# Main.net
KiCad netlist of a schematic drawn in Altium Designer
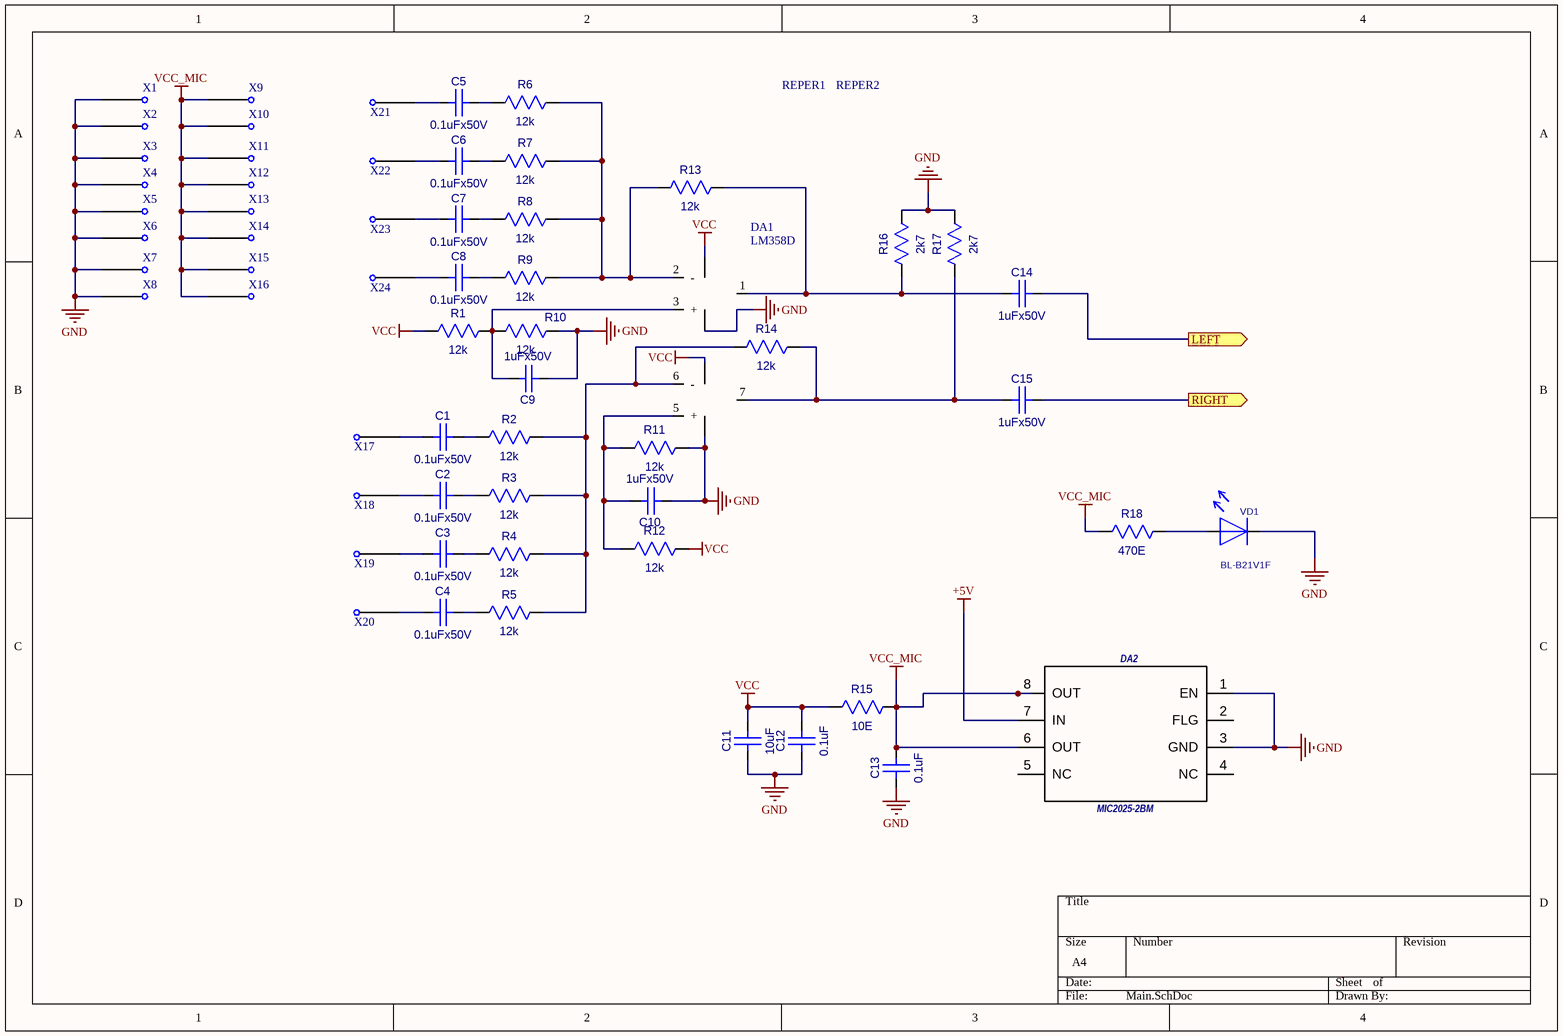
[diagram p0: Main.SchDoc]

(export (version "E")
  (design (tool "Eeschema 10.0.6"))
  (components
    (comp (ref "C1")
      (value "0.1uFx50V")
      (footprint "CC0603-3M")
      (description "CC0603 X7R")
      (libsource (lib "gprs_modem") (part "CC0603"))
    )
    (comp (ref "C2")
      (value "0.1uFx50V")
      (footprint "CC0603-3M")
      (description "CC0603 X7R")
      (libsource (lib "gprs_modem") (part "CC0603"))
    )
    (comp (ref "C3")
      (value "0.1uFx50V")
      (footprint "CC0603-3M")
      (description "CC0603 X7R")
      (libsource (lib "gprs_modem") (part "CC0603"))
    )
    (comp (ref "C4")
      (value "0.1uFx50V")
      (footprint "CC0603-3M")
      (description "CC0603 X7R")
      (libsource (lib "gprs_modem") (part "CC0603"))
    )
    (comp (ref "C5")
      (value "0.1uFx50V")
      (footprint "CC0603-3M")
      (description "CC0603 X7R")
      (libsource (lib "gprs_modem") (part "CC0603"))
    )
    (comp (ref "C6")
      (value "0.1uFx50V")
      (footprint "CC0603-3M")
      (description "CC0603 X7R")
      (libsource (lib "gprs_modem") (part "CC0603"))
    )
    (comp (ref "C7")
      (value "0.1uFx50V")
      (footprint "CC0603-3M")
      (description "CC0603 X7R")
      (libsource (lib "gprs_modem") (part "CC0603"))
    )
    (comp (ref "C8")
      (value "0.1uFx50V")
      (footprint "CC0603-3M")
      (description "CC0603 X7R")
      (libsource (lib "gprs_modem") (part "CC0603"))
    )
    (comp (ref "C9")
      (value "1uFx50V")
      (footprint "CC0603-3M")
      (description "CC0603 X7R")
      (libsource (lib "gprs_modem") (part "CC0603"))
    )
    (comp (ref "C10")
      (value "1uFx50V")
      (footprint "CC0603-3M")
      (description "CC0603 X7R")
      (libsource (lib "gprs_modem") (part "CC0603"))
    )
    (comp (ref "C11")
      (value "10uF")
      (footprint "CC0805-MIDI-2M1")
      (description "CC0805")
      (libsource (lib "gprs_modem") (part "CC0805"))
    )
    (comp (ref "C12")
      (value "0.1uF")
      (footprint "CC0603-3M")
      (description "CC0603")
      (libsource (lib "gprs_modem") (part "CC0603"))
    )
    (comp (ref "C13")
      (value "0.1uF")
      (footprint "CC0603-3M")
      (description "CC0603")
      (libsource (lib "gprs_modem") (part "CC0603"))
    )
    (comp (ref "C14")
      (value "1uFx50V")
      (footprint "CC0603-3M")
      (description "CC0603 X7R")
      (libsource (lib "gprs_modem") (part "CC0603"))
    )
    (comp (ref "C15")
      (value "1uFx50V")
      (footprint "CC0603-3M")
      (description "CC0603 X7R")
      (libsource (lib "gprs_modem") (part "CC0603"))
    )
    (comp (ref "DA1") (value "LM358D") (footprint "SO-8") (libsource (lib "VHF") (part "LM358D")))
    (comp (ref "DA2") (value "MIC2025-2BM") (footprint "SO-8") (libsource (lib "*") (part "MIC2025-2BM")))
    (comp (ref "R1")
      (value "12k")
      (footprint "RC0603-3M")
      (description "RC0603")
      (libsource (lib "gprs_modem") (part "RC0603"))
    )
    (comp (ref "R2")
      (value "12k")
      (footprint "RC0603-3M")
      (description "RC0603")
      (libsource (lib "gprs_modem") (part "RC0603"))
    )
    (comp (ref "R3")
      (value "12k")
      (footprint "RC0603-3M")
      (description "RC0603")
      (libsource (lib "gprs_modem") (part "RC0603"))
    )
    (comp (ref "R4")
      (value "12k")
      (footprint "RC0603-3M")
      (description "RC0603")
      (libsource (lib "gprs_modem") (part "RC0603"))
    )
    (comp (ref "R5")
      (value "12k")
      (footprint "RC0603-3M")
      (description "RC0603")
      (libsource (lib "gprs_modem") (part "RC0603"))
    )
    (comp (ref "R6")
      (value "12k")
      (footprint "RC0603-3M")
      (description "RC0603")
      (libsource (lib "gprs_modem") (part "RC0603"))
    )
    (comp (ref "R7")
      (value "12k")
      (footprint "RC0603-3M")
      (description "RC0603")
      (libsource (lib "gprs_modem") (part "RC0603"))
    )
    (comp (ref "R8")
      (value "12k")
      (footprint "RC0603-3M")
      (description "RC0603")
      (libsource (lib "gprs_modem") (part "RC0603"))
    )
    (comp (ref "R9")
      (value "12k")
      (footprint "RC0603-3M")
      (description "RC0603")
      (libsource (lib "gprs_modem") (part "RC0603"))
    )
    (comp (ref "R10")
      (value "12k")
      (footprint "RC0603-3M")
      (description "RC0603")
      (libsource (lib "gprs_modem") (part "RC0603"))
    )
    (comp (ref "R11")
      (value "12k")
      (footprint "RC0603-3M")
      (description "RC0603")
      (libsource (lib "gprs_modem") (part "RC0603"))
    )
    (comp (ref "R12")
      (value "12k")
      (footprint "RC0603-3M")
      (description "RC0603")
      (libsource (lib "gprs_modem") (part "RC0603"))
    )
    (comp (ref "R13")
      (value "12k")
      (footprint "RC0603-3M")
      (description "RC0603")
      (libsource (lib "gprs_modem") (part "RC0603"))
    )
    (comp (ref "R14")
      (value "12k")
      (footprint "RC0603-3M")
      (description "RC0603")
      (libsource (lib "gprs_modem") (part "RC0603"))
    )
    (comp (ref "R15")
      (value "10E")
      (footprint "RC0805_IPC_NOM")
      (description "RC0805")
      (libsource (lib "gprs_modem") (part "RC0805"))
    )
    (comp (ref "R16")
      (value "2k7")
      (footprint "RC0603-3M")
      (description "RC0603")
      (libsource (lib "gprs_modem") (part "RC0603"))
    )
    (comp (ref "R17")
      (value "2k7")
      (footprint "RC0603-3M")
      (description "RC0603")
      (libsource (lib "gprs_modem") (part "RC0603"))
    )
    (comp (ref "R18")
      (value "470E")
      (footprint "RC0603-3M")
      (description "RC0603")
      (libsource (lib "gprs_modem") (part "RC0603"))
    )
    (comp (ref "REPER1")
      (value "REPER1.2")
      (footprint "REPER1.2")
      (libsource (lib "gprs_modem") (part "REPER1.2"))
    )
    (comp (ref "REPER2")
      (value "REPER1.2")
      (footprint "REPER1.2")
      (libsource (lib "gprs_modem") (part "REPER1.2"))
    )
    (comp (ref "VD1")
      (value "BL-B21V1F")
      (footprint "LED3")
      (description "LED_3")
      (libsource (lib "gprs_modem") (part "LED_3"))
    )
    (comp (ref "X1") (value "PIN_1mm") (footprint "PIN_1mm") (libsource (lib "gprs_modem") (part "PIN_1mm")))
    (comp (ref "X2") (value "PIN_1mm") (footprint "PIN_1mm") (libsource (lib "gprs_modem") (part "PIN_1mm")))
    (comp (ref "X3") (value "PIN_1mm") (footprint "PIN_1mm") (libsource (lib "gprs_modem") (part "PIN_1mm")))
    (comp (ref "X4") (value "PIN_1mm") (footprint "PIN_1mm") (libsource (lib "gprs_modem") (part "PIN_1mm")))
    (comp (ref "X5") (value "PIN_1mm") (footprint "PIN_1mm") (libsource (lib "gprs_modem") (part "PIN_1mm")))
    (comp (ref "X6") (value "PIN_1mm") (footprint "PIN_1mm") (libsource (lib "gprs_modem") (part "PIN_1mm")))
    (comp (ref "X7") (value "PIN_1mm") (footprint "PIN_1mm") (libsource (lib "gprs_modem") (part "PIN_1mm")))
    (comp (ref "X8") (value "PIN_1mm") (footprint "PIN_1mm") (libsource (lib "gprs_modem") (part "PIN_1mm")))
    (comp (ref "X9") (value "PIN_1mm") (footprint "PIN_1mm") (libsource (lib "gprs_modem") (part "PIN_1mm")))
    (comp (ref "X10") (value "PIN_1mm") (footprint "PIN_1mm") (libsource (lib "gprs_modem") (part "PIN_1mm")))
    (comp (ref "X11") (value "PIN_1mm") (footprint "PIN_1mm") (libsource (lib "gprs_modem") (part "PIN_1mm")))
    (comp (ref "X12") (value "PIN_1mm") (footprint "PIN_1mm") (libsource (lib "gprs_modem") (part "PIN_1mm")))
    (comp (ref "X13") (value "PIN_1mm") (footprint "PIN_1mm") (libsource (lib "gprs_modem") (part "PIN_1mm")))
    (comp (ref "X14") (value "PIN_1mm") (footprint "PIN_1mm") (libsource (lib "gprs_modem") (part "PIN_1mm")))
    (comp (ref "X15") (value "PIN_1mm") (footprint "PIN_1mm") (libsource (lib "gprs_modem") (part "PIN_1mm")))
    (comp (ref "X16") (value "PIN_1mm") (footprint "PIN_1mm") (libsource (lib "gprs_modem") (part "PIN_1mm")))
    (comp (ref "X17") (value "PIN_1mm") (footprint "PIN_1mm") (libsource (lib "gprs_modem") (part "PIN_1mm")))
    (comp (ref "X18") (value "PIN_1mm") (footprint "PIN_1mm") (libsource (lib "gprs_modem") (part "PIN_1mm")))
    (comp (ref "X19") (value "PIN_1mm") (footprint "PIN_1mm") (libsource (lib "gprs_modem") (part "PIN_1mm")))
    (comp (ref "X20") (value "PIN_1mm") (footprint "PIN_1mm") (libsource (lib "gprs_modem") (part "PIN_1mm")))
    (comp (ref "X21") (value "PIN_1mm") (footprint "PIN_1mm") (libsource (lib "gprs_modem") (part "PIN_1mm")))
    (comp (ref "X22") (value "PIN_1mm") (footprint "PIN_1mm") (libsource (lib "gprs_modem") (part "PIN_1mm")))
    (comp (ref "X23") (value "PIN_1mm") (footprint "PIN_1mm") (libsource (lib "gprs_modem") (part "PIN_1mm")))
    (comp (ref "X24") (value "PIN_1mm") (footprint "PIN_1mm") (libsource (lib "gprs_modem") (part "PIN_1mm")))
  )
  (nets
    (net (code "1") (name "+5V") (class "Default")
      (node (ref "DA2") (pin "7") (pinfunction "IN_7") (pintype "passive"))
    )
    (net (code "2") (name "/LEFT") (class "Default")
      (node (ref "C14") (pin "2") (pinfunction "B_2") (pintype "passive"))
    )
    (net (code "3") (name "/RIGHT") (class "Default")
      (node (ref "C15") (pin "2") (pinfunction "B_2") (pintype "passive"))
    )
    (net (code "4") (name "GND") (class "Default")
      (node (ref "C10") (pin "1") (pinfunction "A_1") (pintype "passive"))
      (node (ref "C11") (pin "1") (pinfunction "A_1") (pintype "passive"))
      (node (ref "C12") (pin "1") (pinfunction "A_1") (pintype "passive"))
      (node (ref "C13") (pin "1") (pinfunction "A_1") (pintype "passive"))
      (node (ref "C9") (pin "1") (pinfunction "A_1") (pintype "passive"))
      (node (ref "DA1") (pin "4") (pinfunction "Vss_4") (pintype "passive"))
      (node (ref "DA2") (pin "1") (pinfunction "EN_1") (pintype "passive"))
      (node (ref "DA2") (pin "3") (pinfunction "GND_3") (pintype "passive"))
      (node (ref "R10") (pin "2") (pinfunction "B_2") (pintype "passive"))
      (node (ref "R11") (pin "2") (pinfunction "B_2") (pintype "passive"))
      (node (ref "R16") (pin "2") (pinfunction "B_2") (pintype "passive"))
      (node (ref "R17") (pin "2") (pinfunction "B_2") (pintype "passive"))
      (node (ref "VD1") (pin "1") (pintype "passive"))
      (node (ref "X1") (pin "1") (pinfunction "1_1") (pintype "passive"))
      (node (ref "X2") (pin "1") (pinfunction "1_1") (pintype "passive"))
      (node (ref "X3") (pin "1") (pinfunction "1_1") (pintype "passive"))
      (node (ref "X4") (pin "1") (pinfunction "1_1") (pintype "passive"))
      (node (ref "X5") (pin "1") (pinfunction "1_1") (pintype "passive"))
      (node (ref "X6") (pin "1") (pinfunction "1_1") (pintype "passive"))
      (node (ref "X7") (pin "1") (pinfunction "1_1") (pintype "passive"))
      (node (ref "X8") (pin "1") (pinfunction "1_1") (pintype "passive"))
    )
    (net (code "5") (name "Net-(C1-A)") (class "Default")
      (node (ref "C1") (pin "1") (pinfunction "A_1") (pintype "passive"))
      (node (ref "X17") (pin "1") (pinfunction "1_1") (pintype "passive"))
    )
    (net (code "6") (name "Net-(C1-B)") (class "Default")
      (node (ref "C1") (pin "2") (pinfunction "B_2") (pintype "passive"))
      (node (ref "R2") (pin "1") (pinfunction "A_1") (pintype "passive"))
    )
    (net (code "7") (name "Net-(C2-A)") (class "Default")
      (node (ref "C2") (pin "1") (pinfunction "A_1") (pintype "passive"))
      (node (ref "X18") (pin "1") (pinfunction "1_1") (pintype "passive"))
    )
    (net (code "8") (name "Net-(C2-B)") (class "Default")
      (node (ref "C2") (pin "2") (pinfunction "B_2") (pintype "passive"))
      (node (ref "R3") (pin "1") (pinfunction "A_1") (pintype "passive"))
    )
    (net (code "9") (name "Net-(C3-A)") (class "Default")
      (node (ref "C3") (pin "1") (pinfunction "A_1") (pintype "passive"))
      (node (ref "X19") (pin "1") (pinfunction "1_1") (pintype "passive"))
    )
    (net (code "10") (name "Net-(C3-B)") (class "Default")
      (node (ref "C3") (pin "2") (pinfunction "B_2") (pintype "passive"))
      (node (ref "R4") (pin "1") (pinfunction "A_1") (pintype "passive"))
    )
    (net (code "11") (name "Net-(C4-A)") (class "Default")
      (node (ref "C4") (pin "1") (pinfunction "A_1") (pintype "passive"))
      (node (ref "X20") (pin "1") (pinfunction "1_1") (pintype "passive"))
    )
    (net (code "12") (name "Net-(C4-B)") (class "Default")
      (node (ref "C4") (pin "2") (pinfunction "B_2") (pintype "passive"))
      (node (ref "R5") (pin "1") (pinfunction "A_1") (pintype "passive"))
    )
    (net (code "13") (name "Net-(C5-A)") (class "Default")
      (node (ref "C5") (pin "1") (pinfunction "A_1") (pintype "passive"))
      (node (ref "X21") (pin "1") (pinfunction "1_1") (pintype "passive"))
    )
    (net (code "14") (name "Net-(C5-B)") (class "Default")
      (node (ref "C5") (pin "2") (pinfunction "B_2") (pintype "passive"))
      (node (ref "R6") (pin "1") (pinfunction "A_1") (pintype "passive"))
    )
    (net (code "15") (name "Net-(C6-A)") (class "Default")
      (node (ref "C6") (pin "1") (pinfunction "A_1") (pintype "passive"))
      (node (ref "X22") (pin "1") (pinfunction "1_1") (pintype "passive"))
    )
    (net (code "16") (name "Net-(C6-B)") (class "Default")
      (node (ref "C6") (pin "2") (pinfunction "B_2") (pintype "passive"))
      (node (ref "R7") (pin "1") (pinfunction "A_1") (pintype "passive"))
    )
    (net (code "17") (name "Net-(C7-A)") (class "Default")
      (node (ref "C7") (pin "1") (pinfunction "A_1") (pintype "passive"))
      (node (ref "X23") (pin "1") (pinfunction "1_1") (pintype "passive"))
    )
    (net (code "18") (name "Net-(C7-B)") (class "Default")
      (node (ref "C7") (pin "2") (pinfunction "B_2") (pintype "passive"))
      (node (ref "R8") (pin "1") (pinfunction "A_1") (pintype "passive"))
    )
    (net (code "19") (name "Net-(C8-A)") (class "Default")
      (node (ref "C8") (pin "1") (pinfunction "A_1") (pintype "passive"))
      (node (ref "X24") (pin "1") (pinfunction "1_1") (pintype "passive"))
    )
    (net (code "20") (name "Net-(C8-B)") (class "Default")
      (node (ref "C8") (pin "2") (pinfunction "B_2") (pintype "passive"))
      (node (ref "R9") (pin "1") (pinfunction "A_1") (pintype "passive"))
    )
    (net (code "21") (name "Net-(C9-B)") (class "Default")
      (node (ref "C9") (pin "2") (pinfunction "B_2") (pintype "passive"))
      (node (ref "DA1") (pin "3") (pinfunction "+_3") (pintype "passive"))
      (node (ref "R1") (pin "2") (pinfunction "B_2") (pintype "passive"))
      (node (ref "R10") (pin "1") (pinfunction "A_1") (pintype "passive"))
    )
    (net (code "22") (name "Net-(C10-B)") (class "Default")
      (node (ref "C10") (pin "2") (pinfunction "B_2") (pintype "passive"))
      (node (ref "DA1") (pin "5") (pinfunction "+_5") (pintype "passive"))
      (node (ref "R11") (pin "1") (pinfunction "A_1") (pintype "passive"))
      (node (ref "R12") (pin "1") (pinfunction "A_1") (pintype "passive"))
    )
    (net (code "23") (name "Net-(C14-A)") (class "Default")
      (node (ref "C14") (pin "1") (pinfunction "A_1") (pintype "passive"))
      (node (ref "DA1") (pin "1") (pinfunction "Out1_1") (pintype "passive"))
      (node (ref "R13") (pin "2") (pinfunction "B_2") (pintype "passive"))
      (node (ref "R16") (pin "1") (pinfunction "A_1") (pintype "passive"))
    )
    (net (code "24") (name "Net-(C15-A)") (class "Default")
      (node (ref "C15") (pin "1") (pinfunction "A_1") (pintype "passive"))
      (node (ref "DA1") (pin "7") (pinfunction "Out2_7") (pintype "passive"))
      (node (ref "R14") (pin "2") (pinfunction "B_2") (pintype "passive"))
      (node (ref "R17") (pin "1") (pinfunction "A_1") (pintype "passive"))
    )
    (net (code "25") (name "Net-(R13-A)") (class "Default")
      (node (ref "DA1") (pin "2") (pinfunction "-_2") (pintype "passive"))
      (node (ref "R13") (pin "1") (pinfunction "A_1") (pintype "passive"))
      (node (ref "R6") (pin "2") (pinfunction "B_2") (pintype "passive"))
      (node (ref "R7") (pin "2") (pinfunction "B_2") (pintype "passive"))
      (node (ref "R8") (pin "2") (pinfunction "B_2") (pintype "passive"))
      (node (ref "R9") (pin "2") (pinfunction "B_2") (pintype "passive"))
    )
    (net (code "26") (name "Net-(R14-A)") (class "Default")
      (node (ref "DA1") (pin "6") (pinfunction "-_6") (pintype "passive"))
      (node (ref "R14") (pin "1") (pinfunction "A_1") (pintype "passive"))
      (node (ref "R2") (pin "2") (pinfunction "B_2") (pintype "passive"))
      (node (ref "R3") (pin "2") (pinfunction "B_2") (pintype "passive"))
      (node (ref "R4") (pin "2") (pinfunction "B_2") (pintype "passive"))
      (node (ref "R5") (pin "2") (pinfunction "B_2") (pintype "passive"))
    )
    (net (code "27") (name "Net-(R18-B)") (class "Default")
      (node (ref "R18") (pin "2") (pinfunction "B_2") (pintype "passive"))
      (node (ref "VD1") (pin "2") (pintype "passive"))
    )
    (net (code "28") (name "VCC") (class "Default")
      (node (ref "C11") (pin "2") (pinfunction "B_2") (pintype "passive"))
      (node (ref "C12") (pin "2") (pinfunction "B_2") (pintype "passive"))
      (node (ref "DA1") (pin "8") (pinfunction "Vdd_8") (pintype "passive"))
      (node (ref "R1") (pin "1") (pinfunction "A_1") (pintype "passive"))
      (node (ref "R12") (pin "2") (pinfunction "B_2") (pintype "passive"))
      (node (ref "R15") (pin "1") (pinfunction "A_1") (pintype "passive"))
    )
    (net (code "29") (name "VCC_MIC") (class "Default")
      (node (ref "C13") (pin "2") (pinfunction "B_2") (pintype "passive"))
      (node (ref "DA2") (pin "6") (pinfunction "OUT_6") (pintype "passive"))
      (node (ref "DA2") (pin "8") (pinfunction "OUT_8") (pintype "passive"))
      (node (ref "R15") (pin "2") (pinfunction "B_2") (pintype "passive"))
      (node (ref "R18") (pin "1") (pinfunction "A_1") (pintype "passive"))
      (node (ref "X10") (pin "1") (pinfunction "1_1") (pintype "passive"))
      (node (ref "X11") (pin "1") (pinfunction "1_1") (pintype "passive"))
      (node (ref "X12") (pin "1") (pinfunction "1_1") (pintype "passive"))
      (node (ref "X13") (pin "1") (pinfunction "1_1") (pintype "passive"))
      (node (ref "X14") (pin "1") (pinfunction "1_1") (pintype "passive"))
      (node (ref "X15") (pin "1") (pinfunction "1_1") (pintype "passive"))
      (node (ref "X16") (pin "1") (pinfunction "1_1") (pintype "passive"))
      (node (ref "X9") (pin "1") (pinfunction "1_1") (pintype "passive"))
    )
    (net (code "30") (name "unconnected-(DA2-FLG-Pad2)") (class "Default")
      (node (ref "DA2") (pin "2") (pinfunction "FLG_2") (pintype "passive"))
    )
    (net (code "31") (name "unconnected-(DA2-NC-Pad4)") (class "Default")
      (node (ref "DA2") (pin "4") (pinfunction "NC_4") (pintype "passive"))
    )
    (net (code "32") (name "unconnected-(DA2-NC-Pad5)") (class "Default")
      (node (ref "DA2") (pin "5") (pinfunction "NC_5") (pintype "passive"))
    )
    (net (code "33") (name "unconnected-(REPER1-Pad1)") (class "Default")
      (node (ref "REPER1") (pin "1") (pintype "passive"))
    )
    (net (code "34") (name "unconnected-(REPER2-Pad1)") (class "Default")
      (node (ref "REPER2") (pin "1") (pintype "passive"))
    )
  )
)
